# Pyro_Power.net
KiCad netlist of a schematic drawn in Altium Designer
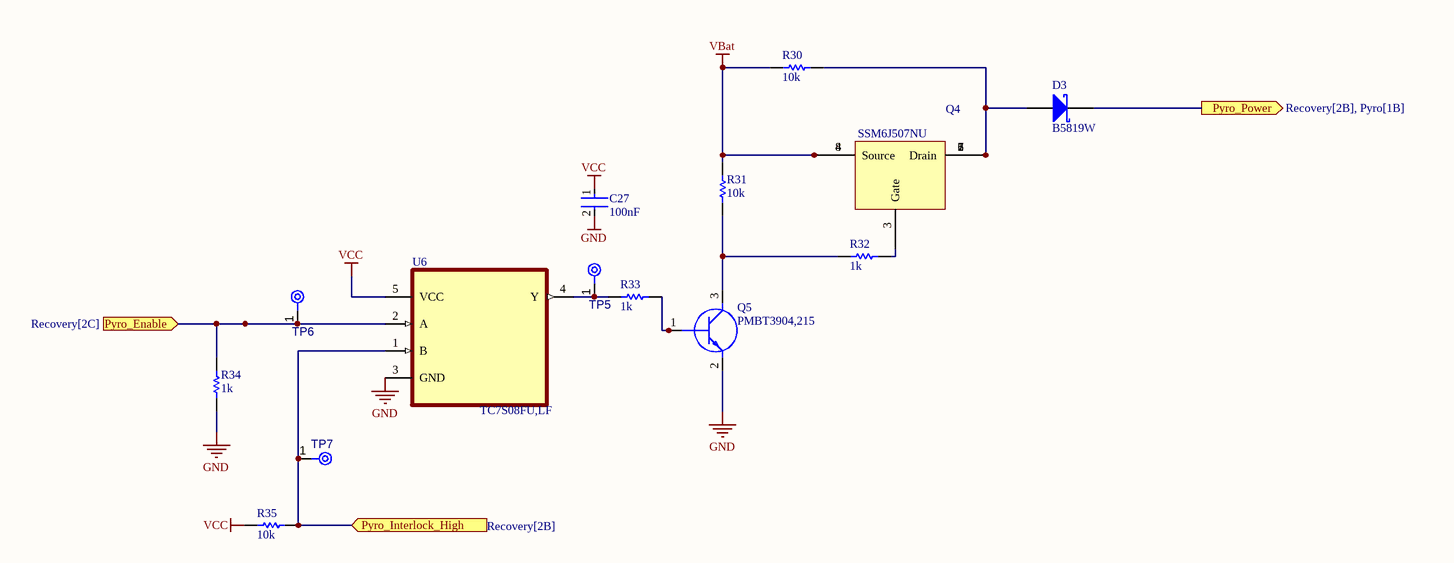
[diagram p0: Pyro_Power.SchDoc]

(export (version "E")
  (design (tool "Eeschema 10.0.6"))
  (components
    (comp (ref "C27")
      (value "100nF")
      (footprint "FP-0603-L_1_6_0_15-W_0_81-IPC_C")
      (description "Generic 0603 Capacitor")
      (fields (field (name "LCSC PART #") "C14663") (field (name "TOLERANCE") "10%"))
      (libsource (lib "StrathSEDS") (part "02cd4be3c70576c341d710602a673aa"))
    )
    (comp (ref "D3")
      (value "B5819W")
      (footprint "MCC-SOD123_V")
      (description "Schottky Barrier Rectifier, 40 V, 1 A, -65 to 125 degC, 2-Pin SOD123, RoHS, Tape and Reel")
      (fields
        (field (name "MANUFACTURER") "Micro Commercial Components")
        (field (name "LCSC PART #") "C8598")
      )
      (libsource (lib "StrathSEDS") (part "DSKY-AK-2"))
    )
    (comp (ref "Q4")
      (value "SSM6J507NU")
      (footprint "SSM6J507NULF")
      (description "MOSFET Small Signal MOSFET V=30V")
      (fields
        (field (name "MOUSER PART NUMBER") "757-SSM6J507NULF")
        (field (name "MANUFACTURER_PART_NUMBER") "SSM6J507NU,LF")
      )
      (libsource (lib "StrathSEDS") (part "c-Symbol-1"))
    )
    (comp (ref "Q5")
      (value "PMBT3904,215")
      (footprint "SOT95P230X110-3N")
      (description "PMBT3904 - NPN switching transistor")
      (fields (field (name "MOUSER PART NUMBER") "771-PMBT3904-T/R") (field (name "LCSC PART #") "C8667"))
      (libsource (lib "StrathSEDS") (part "PMBT3904,215"))
    )
    (comp (ref "R30")
      (value "10k")
      (footprint "RESC1609X50X30ML8T20")
      (description "Generic 0603 Resistor")
      (fields (field (name "TOLERANCE") "0%") (field (name "LCSC PART #") "C25804"))
      (libsource (lib "StrathSEDS") (part "RES-2"))
    )
    (comp (ref "R31")
      (value "10k")
      (footprint "RESC1609X50X30ML8T20")
      (description "Generic 0603 Resistor")
      (fields (field (name "TOLERANCE") "0%") (field (name "LCSC PART #") "C25804"))
      (libsource (lib "StrathSEDS") (part "RES-2"))
    )
    (comp (ref "R32")
      (value "1k")
      (footprint "RESC1609X50X30ML8T20")
      (description "Generic 0603 Resistor")
      (fields (field (name "TOLERANCE") "0%") (field (name "LCSC PART #") "C21190"))
      (libsource (lib "StrathSEDS") (part "RES-2"))
    )
    (comp (ref "R33")
      (value "1k")
      (footprint "RESC1609X50X30ML8T20")
      (description "Generic 0603 Resistor")
      (fields (field (name "TOLERANCE") "0%") (field (name "LCSC PART #") "C21190"))
      (libsource (lib "StrathSEDS") (part "RES-2"))
    )
    (comp (ref "R34")
      (value "1k")
      (footprint "RESC1609X50X30ML8T20")
      (description "Generic 0603 Resistor")
      (fields (field (name "TOLERANCE") "0%") (field (name "LCSC PART #") "C21190"))
      (libsource (lib "StrathSEDS") (part "RES-2"))
    )
    (comp (ref "R35")
      (value "10k")
      (footprint "RESC1609X50X30ML8T20")
      (description "Generic 0603 Resistor")
      (fields (field (name "TOLERANCE") "0%") (field (name "LCSC PART #") "C25804"))
      (libsource (lib "StrathSEDS") (part "RES-2"))
    )
    (comp (ref "TP5")
      (value "TPAD6R")
      (footprint "TP06R")
      (description "0.6mm round")
      (libsource (lib "StrathSEDS") (part "CMP-001-0001-4"))
    )
    (comp (ref "TP6")
      (value "TPAD6R")
      (footprint "TP06R")
      (description "0.6mm round")
      (libsource (lib "StrathSEDS") (part "CMP-001-0001-4"))
    )
    (comp (ref "TP7")
      (value "TPAD6R")
      (footprint "TP06R")
      (description "0.6mm round")
      (libsource (lib "StrathSEDS") (part "CMP-001-0001-4"))
    )
    (comp (ref "U6")
      (value "TC7S08FU,LF")
      (footprint "SOT65P210X110-5N")
      (description "Single 2-input AND gate")
      (fields (field (name "LCSC PART #") "C146362"))
      (libsource (lib "StrathSEDS") (part "74LVC1G08GW,125"))
    )
  )
  (nets
    (net (code "1") (name "/Pyro_Enable") (class "Default")
      (node (ref "R34") (pin "2") (pinfunction "2_2") (pintype "passive"))
      (node (ref "TP6") (pin "1") (pinfunction "TP_1") (pintype "passive"))
      (node (ref "U6") (pin "2") (pinfunction "A_2") (pintype "input"))
    )
    (net (code "2") (name "/Pyro_Interlock_High") (class "Default")
      (node (ref "R35") (pin "2") (pinfunction "2_2") (pintype "passive"))
      (node (ref "TP7") (pin "1") (pinfunction "TP_1") (pintype "passive"))
      (node (ref "U6") (pin "1") (pinfunction "B_1") (pintype "input"))
    )
    (net (code "3") (name "/Pyro_Power") (class "Default")
      (node (ref "D3") (pin "2") (pinfunction "K_2") (pintype "passive"))
    )
    (net (code "4") (name "GND") (class "Default")
      (node (ref "C27") (pin "2") (pinfunction "2_2") (pintype "passive"))
      (node (ref "Q5") (pin "2") (pinfunction "E_2") (pintype "passive"))
      (node (ref "R34") (pin "1") (pinfunction "1_1") (pintype "passive"))
      (node (ref "U6") (pin "3") (pinfunction "GND_3") (pintype "passive"))
    )
    (net (code "5") (name "Net-(D3-A)") (class "Default")
      (node (ref "D3") (pin "1") (pinfunction "A_1") (pintype "passive"))
      (node (ref "Q4") (pin "1") (pinfunction "Drain_1") (pintype "passive"))
      (node (ref "Q4") (pin "2") (pinfunction "2_2") (pintype "passive"))
      (node (ref "Q4") (pin "5") (pinfunction "5_5") (pintype "passive"))
      (node (ref "Q4") (pin "6") (pinfunction "6_6") (pintype "passive"))
      (node (ref "Q4") (pin "7") (pinfunction "7_7") (pintype "passive"))
      (node (ref "R30") (pin "2") (pinfunction "2_2") (pintype "passive"))
    )
    (net (code "6") (name "Net-(Q4-Gate)") (class "Default")
      (node (ref "Q4") (pin "3") (pinfunction "Gate_3") (pintype "passive"))
      (node (ref "R32") (pin "1") (pinfunction "1_1") (pintype "passive"))
    )
    (net (code "7") (name "Net-(Q5-B)") (class "Default")
      (node (ref "Q5") (pin "1") (pinfunction "B_1") (pintype "passive"))
      (node (ref "R33") (pin "1") (pinfunction "1_1") (pintype "passive"))
    )
    (net (code "8") (name "Net-(Q5-C)") (class "Default")
      (node (ref "Q5") (pin "3") (pinfunction "C_3") (pintype "passive"))
      (node (ref "R31") (pin "1") (pinfunction "1_1") (pintype "passive"))
      (node (ref "R32") (pin "2") (pinfunction "2_2") (pintype "passive"))
    )
    (net (code "9") (name "Net-(TP5-TP)") (class "Default")
      (node (ref "R33") (pin "2") (pinfunction "2_2") (pintype "passive"))
      (node (ref "TP5") (pin "1") (pinfunction "TP_1") (pintype "passive"))
      (node (ref "U6") (pin "4") (pinfunction "Y_4") (pintype "output"))
    )
    (net (code "10") (name "VBat") (class "Default")
      (node (ref "Q4") (pin "4") (pinfunction "Source_4") (pintype "passive"))
      (node (ref "Q4") (pin "8") (pinfunction "8_8") (pintype "passive"))
      (node (ref "R30") (pin "1") (pinfunction "1_1") (pintype "passive"))
      (node (ref "R31") (pin "2") (pinfunction "2_2") (pintype "passive"))
    )
    (net (code "11") (name "VCC") (class "Default")
      (node (ref "C27") (pin "1") (pinfunction "1_1") (pintype "passive"))
      (node (ref "R35") (pin "1") (pinfunction "1_1") (pintype "passive"))
      (node (ref "U6") (pin "5") (pinfunction "VCC_5") (pintype "power_in"))
    )
  )
)
